# working.net
KiCad netlist of a schematic drawn in EAGLE
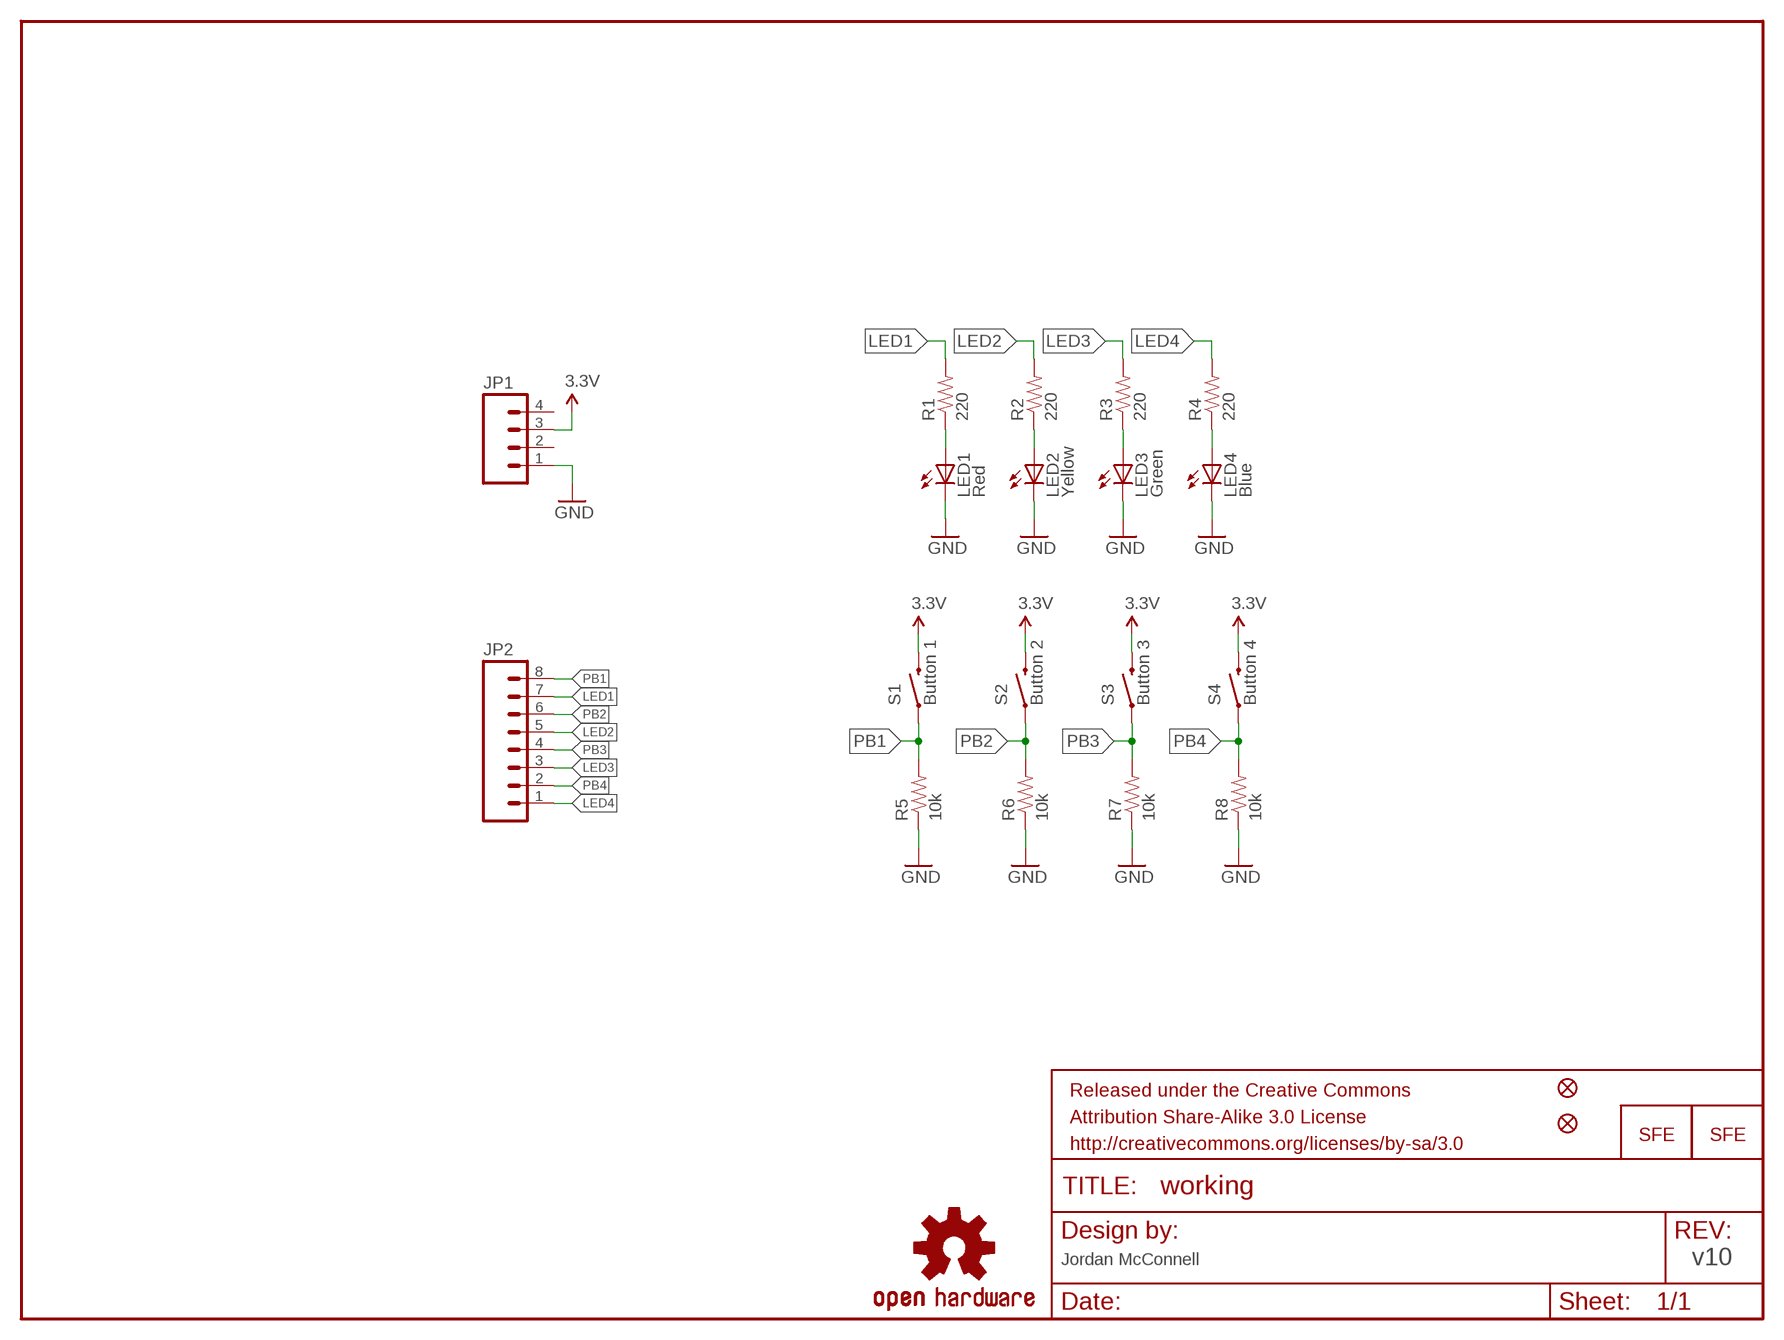
[diagram p0: schematic, sheet 1]

(export (version "E")
  (design (tool "Eeschema 10.0.6"))
  (components
    (comp (ref "FRAME1")
      (value "FRAME-LETTER")
      (footprint "eagle-import:CREATIVE_COMMONS")
      (libsource (lib "eagle-import") (part "FRAME-LETTER"))
    )
    (comp (ref "JP1")
      (value "M04PTH")
      (footprint "eagle-import:1X04")
      (libsource (lib "eagle-import") (part "M04PTH"))
    )
    (comp (ref "JP2")
      (value "M081X08")
      (footprint "eagle-import:1X08")
      (libsource (lib "eagle-import") (part "M081X08"))
    )
    (comp (ref "JP3")
      (value "LOGO-SFESK")
      (footprint "eagle-import:SFE-LOGO-FLAME")
      (libsource (lib "eagle-import") (part "LOGO-SFESK"))
    )
    (comp (ref "JP4")
      (value "LOGO-SFENEW")
      (footprint "eagle-import:SFE-NEW-WEBLOGO")
      (libsource (lib "eagle-import") (part "LOGO-SFENEW"))
    )
    (comp (ref "JP5")
      (value "FIDUCIALUFIDUCIAL")
      (footprint "eagle-import:MICRO-FIDUCIAL")
      (libsource (lib "eagle-import") (part "FIDUCIALUFIDUCIAL"))
    )
    (comp (ref "JP6")
      (value "FIDUCIALUFIDUCIAL")
      (footprint "eagle-import:MICRO-FIDUCIAL")
      (libsource (lib "eagle-import") (part "FIDUCIALUFIDUCIAL"))
    )
    (comp (ref "LED1")
      (value "Red")
      (footprint "eagle-import:LED-0603")
      (libsource (lib "eagle-import") (part "LED0603"))
    )
    (comp (ref "LED2")
      (value "Yellow")
      (footprint "eagle-import:LED-0603")
      (libsource (lib "eagle-import") (part "LED0603"))
    )
    (comp (ref "LED3")
      (value "Green")
      (footprint "eagle-import:LED-0603")
      (libsource (lib "eagle-import") (part "LED0603"))
    )
    (comp (ref "LED4")
      (value "Blue")
      (footprint "eagle-import:LED-0603")
      (libsource (lib "eagle-import") (part "LED0603"))
    )
    (comp (ref "R1")
      (value "220")
      (footprint "eagle-import:0402-RES")
      (libsource (lib "eagle-import") (part "RESISTOR0402-RES"))
    )
    (comp (ref "R2")
      (value "220")
      (footprint "eagle-import:0402-RES")
      (libsource (lib "eagle-import") (part "RESISTOR0402-RES"))
    )
    (comp (ref "R3")
      (value "220")
      (footprint "eagle-import:0402-RES")
      (libsource (lib "eagle-import") (part "RESISTOR0402-RES"))
    )
    (comp (ref "R4")
      (value "220")
      (footprint "eagle-import:0402-RES")
      (libsource (lib "eagle-import") (part "RESISTOR0402-RES"))
    )
    (comp (ref "R5")
      (value "10k")
      (footprint "eagle-import:0402-RES")
      (libsource (lib "eagle-import") (part "RESISTOR0402-RES"))
    )
    (comp (ref "R6")
      (value "10k")
      (footprint "eagle-import:0402-RES")
      (libsource (lib "eagle-import") (part "RESISTOR0402-RES"))
    )
    (comp (ref "R7")
      (value "10k")
      (footprint "eagle-import:0402-RES")
      (libsource (lib "eagle-import") (part "RESISTOR0402-RES"))
    )
    (comp (ref "R8")
      (value "10k")
      (footprint "eagle-import:0402-RES")
      (libsource (lib "eagle-import") (part "RESISTOR0402-RES"))
    )
    (comp (ref "S1")
      (value "Button 1")
      (footprint "eagle-import:TACTILE_SWITCH_SMD")
      (libsource (lib "eagle-import") (part "SWITCH-MOMENTARY-2SMD"))
    )
    (comp (ref "S2")
      (value "Button 2")
      (footprint "eagle-import:TACTILE_SWITCH_SMD")
      (libsource (lib "eagle-import") (part "SWITCH-MOMENTARY-2SMD"))
    )
    (comp (ref "S3")
      (value "Button 3")
      (footprint "eagle-import:TACTILE_SWITCH_SMD")
      (libsource (lib "eagle-import") (part "SWITCH-MOMENTARY-2SMD"))
    )
    (comp (ref "S4")
      (value "Button 4")
      (footprint "eagle-import:TACTILE_SWITCH_SMD")
      (libsource (lib "eagle-import") (part "SWITCH-MOMENTARY-2SMD"))
    )
    (comp (ref "U$1")
      (value "OSHW-LOGOS")
      (footprint "eagle-import:OSHW-LOGO-S")
      (libsource (lib "eagle-import") (part "OSHW-LOGOS"))
    )
  )
  (nets
    (net (code "1") (name "3.3V") (class "Default")
      (node (ref "JP1") (pin "3") (pinfunction "3_3") (pintype "passive"))
      (node (ref "S1") (pin "3") (pinfunction "2_3") (pintype "passive"))
      (node (ref "S2") (pin "3") (pinfunction "2_3") (pintype "passive"))
      (node (ref "S3") (pin "3") (pinfunction "2_3") (pintype "passive"))
      (node (ref "S4") (pin "3") (pinfunction "2_3") (pintype "passive"))
    )
    (net (code "2") (name "GND") (class "Default")
      (node (ref "JP1") (pin "1") (pinfunction "1_1") (pintype "passive"))
      (node (ref "LED1") (pin "C") (pinfunction "C_C") (pintype "passive"))
      (node (ref "LED2") (pin "C") (pinfunction "C_C") (pintype "passive"))
      (node (ref "LED3") (pin "C") (pinfunction "C_C") (pintype "passive"))
      (node (ref "LED4") (pin "C") (pinfunction "C_C") (pintype "passive"))
      (node (ref "R5") (pin "1") (pinfunction "1_1") (pintype "passive"))
      (node (ref "R6") (pin "1") (pinfunction "1_1") (pintype "passive"))
      (node (ref "R7") (pin "1") (pinfunction "1_1") (pintype "passive"))
      (node (ref "R8") (pin "1") (pinfunction "1_1") (pintype "passive"))
    )
    (net (code "3") (name "LED1") (class "Default")
      (node (ref "JP2") (pin "7") (pinfunction "7_7") (pintype "passive"))
      (node (ref "R1") (pin "2") (pinfunction "2_2") (pintype "passive"))
    )
    (net (code "4") (name "LED2") (class "Default")
      (node (ref "JP2") (pin "5") (pinfunction "5_5") (pintype "passive"))
      (node (ref "R2") (pin "2") (pinfunction "2_2") (pintype "passive"))
    )
    (net (code "5") (name "LED3") (class "Default")
      (node (ref "JP2") (pin "3") (pinfunction "3_3") (pintype "passive"))
      (node (ref "R3") (pin "2") (pinfunction "2_2") (pintype "passive"))
    )
    (net (code "6") (name "LED4") (class "Default")
      (node (ref "JP2") (pin "1") (pinfunction "1_1") (pintype "passive"))
      (node (ref "R4") (pin "2") (pinfunction "2_2") (pintype "passive"))
    )
    (net (code "7") (name "Net-(LED1-PadA)") (class "Default")
      (node (ref "LED1") (pin "A") (pinfunction "A_A") (pintype "passive"))
      (node (ref "R1") (pin "1") (pinfunction "1_1") (pintype "passive"))
    )
    (net (code "8") (name "Net-(LED2-PadA)") (class "Default")
      (node (ref "LED2") (pin "A") (pinfunction "A_A") (pintype "passive"))
      (node (ref "R2") (pin "1") (pinfunction "1_1") (pintype "passive"))
    )
    (net (code "9") (name "Net-(LED3-PadA)") (class "Default")
      (node (ref "LED3") (pin "A") (pinfunction "A_A") (pintype "passive"))
      (node (ref "R3") (pin "1") (pinfunction "1_1") (pintype "passive"))
    )
    (net (code "10") (name "Net-(LED4-PadA)") (class "Default")
      (node (ref "LED4") (pin "A") (pinfunction "A_A") (pintype "passive"))
      (node (ref "R4") (pin "1") (pinfunction "1_1") (pintype "passive"))
    )
    (net (code "11") (name "PB1") (class "Default")
      (node (ref "JP2") (pin "8") (pinfunction "8_8") (pintype "passive"))
      (node (ref "R5") (pin "2") (pinfunction "2_2") (pintype "passive"))
      (node (ref "S1") (pin "1") (pinfunction "1_1") (pintype "passive"))
    )
    (net (code "12") (name "PB2") (class "Default")
      (node (ref "JP2") (pin "6") (pinfunction "6_6") (pintype "passive"))
      (node (ref "R6") (pin "2") (pinfunction "2_2") (pintype "passive"))
      (node (ref "S2") (pin "1") (pinfunction "1_1") (pintype "passive"))
    )
    (net (code "13") (name "PB3") (class "Default")
      (node (ref "JP2") (pin "4") (pinfunction "4_4") (pintype "passive"))
      (node (ref "R7") (pin "2") (pinfunction "2_2") (pintype "passive"))
      (node (ref "S3") (pin "1") (pinfunction "1_1") (pintype "passive"))
    )
    (net (code "14") (name "PB4") (class "Default")
      (node (ref "JP2") (pin "2") (pinfunction "2_2") (pintype "passive"))
      (node (ref "R8") (pin "2") (pinfunction "2_2") (pintype "passive"))
      (node (ref "S4") (pin "1") (pinfunction "1_1") (pintype "passive"))
    )
    (net (code "15") (name "unconnected-(JP1-Pad2)") (class "Default")
      (node (ref "JP1") (pin "2") (pinfunction "2_2") (pintype "passive"))
    )
    (net (code "16") (name "unconnected-(JP1-Pad4)") (class "Default")
      (node (ref "JP1") (pin "4") (pinfunction "4_4") (pintype "passive"))
    )
  )
)
